# Sensors.net
KiCad netlist of a schematic drawn in Altium Designer
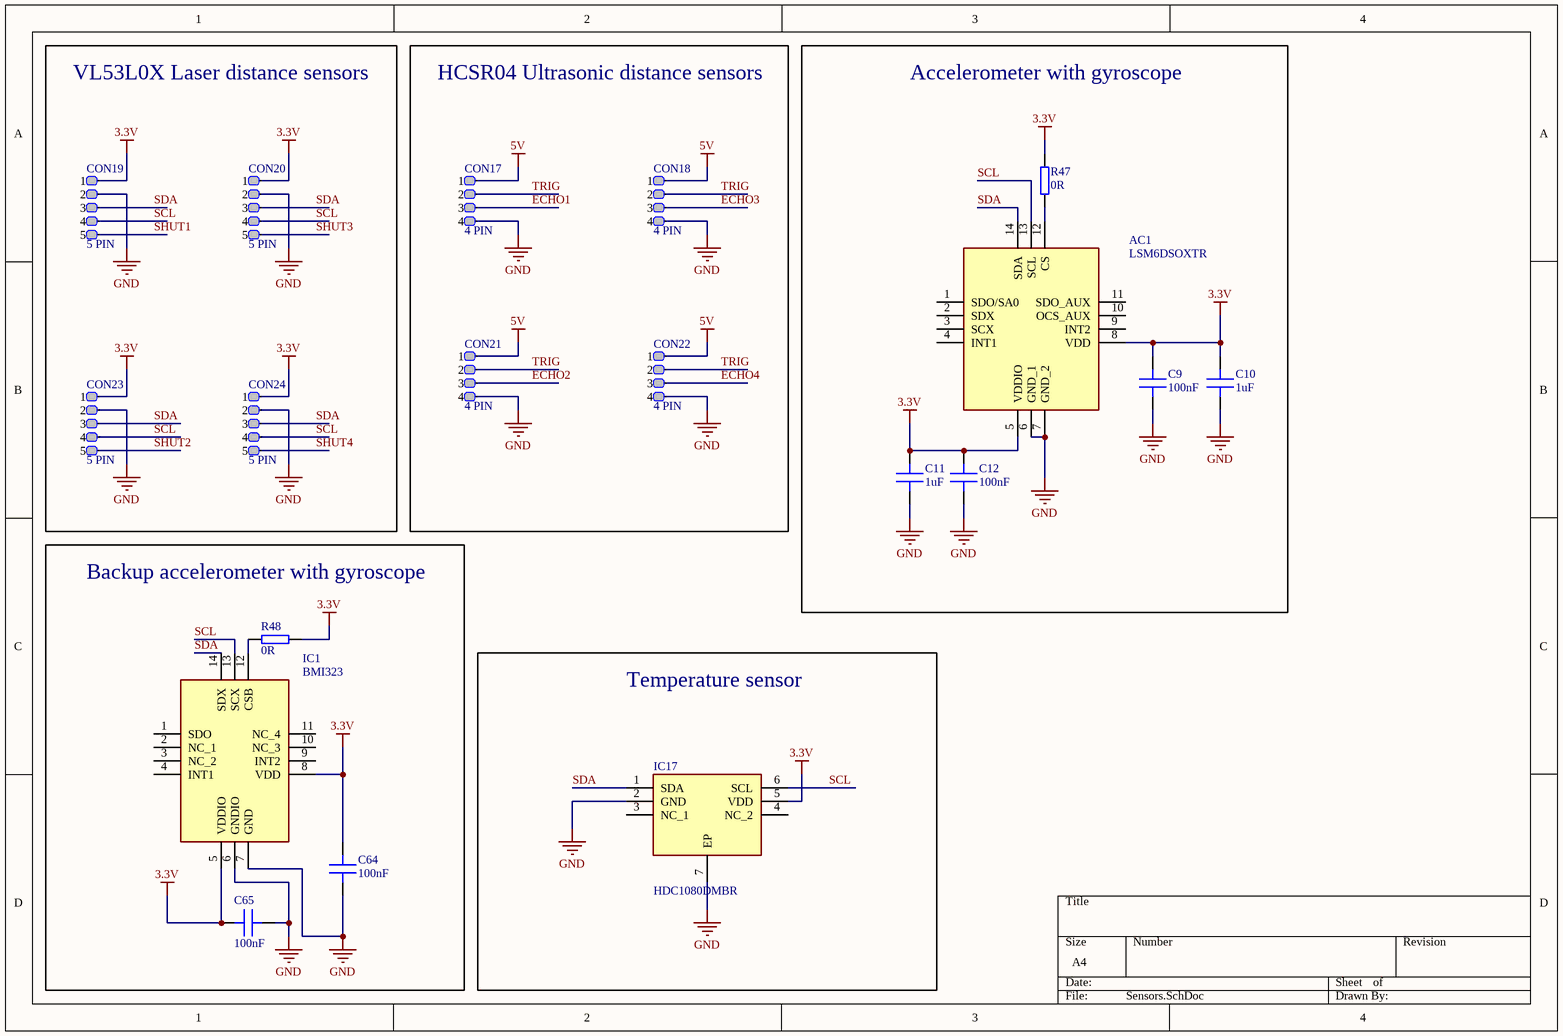
[diagram p0: Sensors.SchDoc]

(export (version "E")
  (design (tool "Eeschema 10.0.6"))
  (components
    (comp (ref "AC1")
      (value "LSM6DSOXTR")
      (footprint "SamacSys:LGA-14_1")
      (description "Accelerometer")
      (fields (field (name "MOUSER PART NUMBER") "511-LSM6DSOXTR"))
      (libsource (lib "caravan_sch_lib") (part "LSM6DSOXTR"))
    )
    (comp (ref "C9")
      (value "100nF")
      (footprint "C 0402")
      (description "MLCC Capacitor")
      (libsource (lib "Components") (part "Capacitor"))
    )
    (comp (ref "C10")
      (value "1uF")
      (footprint "C 0402")
      (description "MLCC Capacitor")
      (libsource (lib "Components") (part "Capacitor"))
    )
    (comp (ref "C11")
      (value "1uF")
      (footprint "C 0402")
      (description "MLCC Capacitor")
      (libsource (lib "Components") (part "Capacitor"))
    )
    (comp (ref "C12")
      (value "100nF")
      (footprint "C 0402")
      (description "MLCC Capacitor")
      (libsource (lib "Components") (part "Capacitor"))
    )
    (comp (ref "C64")
      (value "100nF")
      (footprint "C 0402")
      (description "MLCC Capacitor")
      (libsource (lib "Components") (part "Capacitor"))
    )
    (comp (ref "C65")
      (value "100nF")
      (footprint "C 0402")
      (description "MLCC Capacitor")
      (libsource (lib "Components") (part "Capacitor"))
    )
    (comp (ref "CON17")
      (value "4 PIN")
      (footprint "Goldpin 2.54 4P")
      (libsource (lib "Connectors") (part "4 PIN"))
    )
    (comp (ref "CON18")
      (value "4 PIN")
      (footprint "Goldpin 2.54 4P")
      (libsource (lib "Connectors") (part "4 PIN"))
    )
    (comp (ref "CON19")
      (value "5 PIN")
      (footprint "Goldpin 2.54mm  5Pin")
      (libsource (lib "Connectors") (part "5 PIN"))
    )
    (comp (ref "CON20")
      (value "5 PIN")
      (footprint "Goldpin 2.54mm  5Pin")
      (libsource (lib "Connectors") (part "5 PIN"))
    )
    (comp (ref "CON21")
      (value "4 PIN")
      (footprint "Goldpin 2.54 4P")
      (libsource (lib "Connectors") (part "4 PIN"))
    )
    (comp (ref "CON22")
      (value "4 PIN")
      (footprint "Goldpin 2.54 4P")
      (libsource (lib "Connectors") (part "4 PIN"))
    )
    (comp (ref "CON23")
      (value "5 PIN")
      (footprint "Goldpin 2.54mm  5Pin")
      (libsource (lib "Connectors") (part "5 PIN"))
    )
    (comp (ref "CON24")
      (value "5 PIN")
      (footprint "Goldpin 2.54mm  5Pin")
      (libsource (lib "Connectors") (part "5 PIN"))
    )
    (comp (ref "IC1")
      (value "BMI323")
      (footprint "SamacSys:BMI323")
      (description "Integrated Circuit")
      (fields (field (name "MOUSER PART NUMBER") "262-BMI323"))
      (libsource (lib "*") (part "BMI323"))
    )
    (comp (ref "IC17")
      (value "HDC1080DMBR")
      (footprint "caravan_pcb_lib:SON100P300X300X80-7N-D")
      (description "Integrated Circuit")
      (fields (field (name "MOUSER PART NUMBER") "595-HDC1080DMBR"))
      (libsource (lib "caravan_sch_lib") (part "HDC1080DMBR"))
    )
    (comp (ref "R47")
      (value "0R")
      (footprint "R 0402")
      (description "General pourpouse resistor")
      (libsource (lib "Components") (part "Resistor"))
    )
    (comp (ref "R48")
      (value "0R")
      (footprint "R 0402")
      (description "General pourpouse resistor")
      (libsource (lib "Components") (part "Resistor"))
    )
  )
  (nets
    (net (code "1") (name "/ECHO1") (class "Default")
      (node (ref "CON17") (pin "3") (pinfunction "3_3") (pintype "passive"))
    )
    (net (code "2") (name "/ECHO2") (class "Default")
      (node (ref "CON21") (pin "3") (pinfunction "3_3") (pintype "passive"))
    )
    (net (code "3") (name "/ECHO3") (class "Default")
      (node (ref "CON18") (pin "3") (pinfunction "3_3") (pintype "passive"))
    )
    (net (code "4") (name "/ECHO4") (class "Default")
      (node (ref "CON22") (pin "3") (pinfunction "3_3") (pintype "passive"))
    )
    (net (code "5") (name "/SCL") (class "Default")
      (node (ref "AC1") (pin "13") (pinfunction "SCL_13") (pintype "passive"))
      (node (ref "CON19") (pin "4") (pinfunction "4_4") (pintype "passive"))
      (node (ref "CON20") (pin "4") (pinfunction "4_4") (pintype "passive"))
      (node (ref "CON23") (pin "4") (pinfunction "4_4") (pintype "passive"))
      (node (ref "CON24") (pin "4") (pinfunction "4_4") (pintype "passive"))
      (node (ref "IC1") (pin "13") (pinfunction "SCX_13") (pintype "passive"))
      (node (ref "IC17") (pin "6") (pinfunction "SCL_6") (pintype "passive"))
    )
    (net (code "6") (name "/SDA") (class "Default")
      (node (ref "AC1") (pin "14") (pinfunction "SDA_14") (pintype "passive"))
      (node (ref "CON19") (pin "3") (pinfunction "3_3") (pintype "passive"))
      (node (ref "CON20") (pin "3") (pinfunction "3_3") (pintype "passive"))
      (node (ref "CON23") (pin "3") (pinfunction "3_3") (pintype "passive"))
      (node (ref "CON24") (pin "3") (pinfunction "3_3") (pintype "passive"))
      (node (ref "IC1") (pin "14") (pinfunction "SDX_14") (pintype "passive"))
      (node (ref "IC17") (pin "1") (pinfunction "SDA_1") (pintype "passive"))
    )
    (net (code "7") (name "/SHUT1") (class "Default")
      (node (ref "CON19") (pin "5") (pinfunction "5_5") (pintype "passive"))
    )
    (net (code "8") (name "/SHUT2") (class "Default")
      (node (ref "CON23") (pin "5") (pinfunction "5_5") (pintype "passive"))
    )
    (net (code "9") (name "/SHUT3") (class "Default")
      (node (ref "CON20") (pin "5") (pinfunction "5_5") (pintype "passive"))
    )
    (net (code "10") (name "/SHUT4") (class "Default")
      (node (ref "CON24") (pin "5") (pinfunction "5_5") (pintype "passive"))
    )
    (net (code "11") (name "/TRIG") (class "Default")
      (node (ref "CON17") (pin "2") (pinfunction "2_2") (pintype "passive"))
      (node (ref "CON18") (pin "2") (pinfunction "2_2") (pintype "passive"))
      (node (ref "CON21") (pin "2") (pinfunction "2_2") (pintype "passive"))
      (node (ref "CON22") (pin "2") (pinfunction "2_2") (pintype "passive"))
    )
    (net (code "12") (name "3.3V") (class "Default")
      (node (ref "AC1") (pin "5") (pinfunction "VDDIO_5") (pintype "passive"))
      (node (ref "AC1") (pin "8") (pinfunction "VDD_8") (pintype "passive"))
      (node (ref "C10") (pin "1") (pinfunction "1_1") (pintype "passive"))
      (node (ref "C11") (pin "1") (pinfunction "1_1") (pintype "passive"))
      (node (ref "C12") (pin "1") (pinfunction "1_1") (pintype "passive"))
      (node (ref "C64") (pin "2") (pinfunction "2_2") (pintype "passive"))
      (node (ref "C65") (pin "1") (pinfunction "1_1") (pintype "passive"))
      (node (ref "C9") (pin "1") (pinfunction "1_1") (pintype "passive"))
      (node (ref "CON19") (pin "1") (pinfunction "1_1") (pintype "passive"))
      (node (ref "CON20") (pin "1") (pinfunction "1_1") (pintype "passive"))
      (node (ref "CON23") (pin "1") (pinfunction "1_1") (pintype "passive"))
      (node (ref "CON24") (pin "1") (pinfunction "1_1") (pintype "passive"))
      (node (ref "IC1") (pin "5") (pinfunction "VDDIO_5") (pintype "passive"))
      (node (ref "IC1") (pin "8") (pinfunction "VDD_8") (pintype "passive"))
      (node (ref "IC17") (pin "5") (pinfunction "VDD_5") (pintype "passive"))
      (node (ref "R47") (pin "2") (pinfunction "2_2") (pintype "passive"))
      (node (ref "R48") (pin "2") (pinfunction "2_2") (pintype "passive"))
    )
    (net (code "13") (name "5V") (class "Default")
      (node (ref "CON17") (pin "1") (pinfunction "1_1") (pintype "passive"))
      (node (ref "CON18") (pin "1") (pinfunction "1_1") (pintype "passive"))
      (node (ref "CON21") (pin "1") (pinfunction "1_1") (pintype "passive"))
      (node (ref "CON22") (pin "1") (pinfunction "1_1") (pintype "passive"))
    )
    (net (code "14") (name "GND") (class "Default")
      (node (ref "AC1") (pin "6") (pinfunction "GND_1_6") (pintype "passive"))
      (node (ref "AC1") (pin "7") (pinfunction "GND_2_7") (pintype "passive"))
      (node (ref "C10") (pin "2") (pinfunction "2_2") (pintype "passive"))
      (node (ref "C11") (pin "2") (pinfunction "2_2") (pintype "passive"))
      (node (ref "C12") (pin "2") (pinfunction "2_2") (pintype "passive"))
      (node (ref "C64") (pin "1") (pinfunction "1_1") (pintype "passive"))
      (node (ref "C65") (pin "2") (pinfunction "2_2") (pintype "passive"))
      (node (ref "C9") (pin "2") (pinfunction "2_2") (pintype "passive"))
      (node (ref "CON17") (pin "4") (pinfunction "4_4") (pintype "passive"))
      (node (ref "CON18") (pin "4") (pinfunction "4_4") (pintype "passive"))
      (node (ref "CON19") (pin "2") (pinfunction "2_2") (pintype "passive"))
      (node (ref "CON20") (pin "2") (pinfunction "2_2") (pintype "passive"))
      (node (ref "CON21") (pin "4") (pinfunction "4_4") (pintype "passive"))
      (node (ref "CON22") (pin "4") (pinfunction "4_4") (pintype "passive"))
      (node (ref "CON23") (pin "2") (pinfunction "2_2") (pintype "passive"))
      (node (ref "CON24") (pin "2") (pinfunction "2_2") (pintype "passive"))
      (node (ref "IC1") (pin "6") (pinfunction "GNDIO_6") (pintype "passive"))
      (node (ref "IC1") (pin "7") (pinfunction "GND_7") (pintype "passive"))
      (node (ref "IC17") (pin "2") (pinfunction "GND_2") (pintype "passive"))
      (node (ref "IC17") (pin "7") (pinfunction "EP_7") (pintype "passive"))
    )
    (net (code "15") (name "Net-(AC1-CS)") (class "Default")
      (node (ref "AC1") (pin "12") (pinfunction "CS_12") (pintype "passive"))
      (node (ref "R47") (pin "1") (pinfunction "1_1") (pintype "passive"))
    )
    (net (code "16") (name "Net-(IC1-CSB)") (class "Default")
      (node (ref "IC1") (pin "12") (pinfunction "CSB_12") (pintype "passive"))
      (node (ref "R48") (pin "1") (pinfunction "1_1") (pintype "passive"))
    )
    (net (code "17") (name "unconnected-(AC1-INT1-Pad4)") (class "Default")
      (node (ref "AC1") (pin "4") (pinfunction "INT1_4") (pintype "passive"))
    )
    (net (code "18") (name "unconnected-(AC1-INT2-Pad9)") (class "Default")
      (node (ref "AC1") (pin "9") (pinfunction "INT2_9") (pintype "passive"))
    )
    (net (code "19") (name "unconnected-(AC1-OCS_AUX-Pad10)") (class "Default")
      (node (ref "AC1") (pin "10") (pinfunction "OCS_AUX_10") (pintype "passive"))
    )
    (net (code "20") (name "unconnected-(AC1-SCX-Pad3)") (class "Default")
      (node (ref "AC1") (pin "3") (pinfunction "SCX_3") (pintype "passive"))
    )
    (net (code "21") (name "unconnected-(AC1-SDO_AUX-Pad11)") (class "Default")
      (node (ref "AC1") (pin "11") (pinfunction "SDO_AUX_11") (pintype "passive"))
    )
    (net (code "22") (name "unconnected-(AC1-SDO{slash}SA0-Pad1)") (class "Default")
      (node (ref "AC1") (pin "1") (pinfunction "SDO/SA0_1") (pintype "passive"))
    )
    (net (code "23") (name "unconnected-(AC1-SDX-Pad2)") (class "Default")
      (node (ref "AC1") (pin "2") (pinfunction "SDX_2") (pintype "passive"))
    )
    (net (code "24") (name "unconnected-(IC1-INT1-Pad4)") (class "Default")
      (node (ref "IC1") (pin "4") (pinfunction "INT1_4") (pintype "passive"))
    )
    (net (code "25") (name "unconnected-(IC1-INT2-Pad9)") (class "Default")
      (node (ref "IC1") (pin "9") (pinfunction "INT2_9") (pintype "passive"))
    )
    (net (code "26") (name "unconnected-(IC1-NC_1-Pad2)") (class "Default")
      (node (ref "IC1") (pin "2") (pinfunction "NC_1_2") (pintype "passive"))
    )
    (net (code "27") (name "unconnected-(IC1-NC_2-Pad3)") (class "Default")
      (node (ref "IC1") (pin "3") (pinfunction "NC_2_3") (pintype "passive"))
    )
    (net (code "28") (name "unconnected-(IC1-NC_3-Pad10)") (class "Default")
      (node (ref "IC1") (pin "10") (pinfunction "NC_3_10") (pintype "passive"))
    )
    (net (code "29") (name "unconnected-(IC1-NC_4-Pad11)") (class "Default")
      (node (ref "IC1") (pin "11") (pinfunction "NC_4_11") (pintype "passive"))
    )
    (net (code "30") (name "unconnected-(IC1-SDO-Pad1)") (class "Default")
      (node (ref "IC1") (pin "1") (pinfunction "SDO_1") (pintype "passive"))
    )
    (net (code "31") (name "unconnected-(IC17-NC_1-Pad3)") (class "Default")
      (node (ref "IC17") (pin "3") (pinfunction "NC_1_3") (pintype "passive"))
    )
    (net (code "32") (name "unconnected-(IC17-NC_2-Pad4)") (class "Default")
      (node (ref "IC17") (pin "4") (pinfunction "NC_2_4") (pintype "passive"))
    )
  )
)
